# attinier84-motherboard-mk-3_0.net
KiCad netlist of a schematic drawn in EAGLE
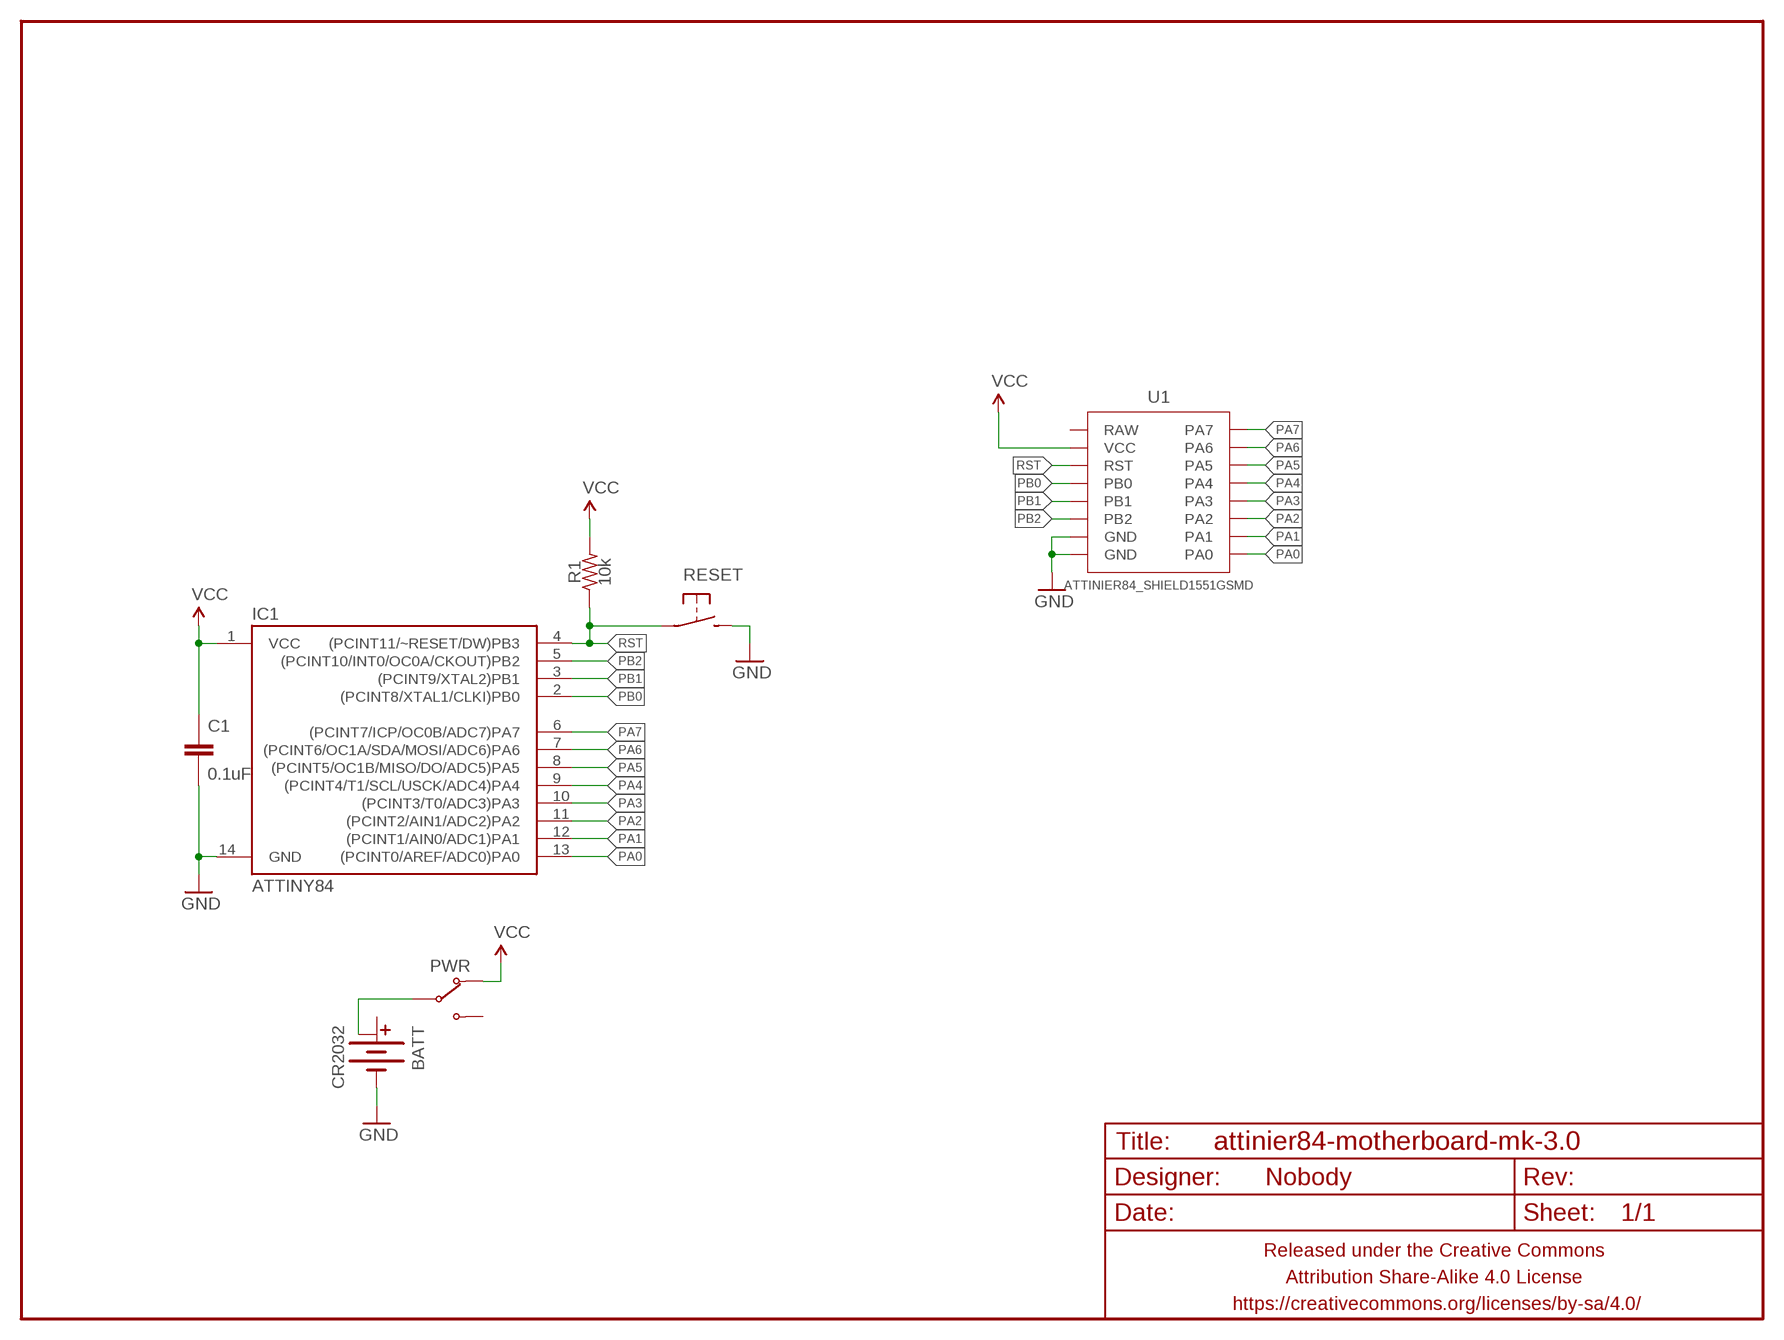
[diagram p0: schematic, sheet 1]

(export (version "E")
  (design (tool "Eeschema 10.0.6"))
  (components
    (comp (ref "BATT")
      (value "CR2032")
      (footprint "eagle-import:BATTCON_20MM_MINE")
      (libsource (lib "eagle-import") (part "BATTERY-COINCR2032_SMD"))
    )
    (comp (ref "C1")
      (value "0.1uF")
      (footprint "eagle-import:C0805")
      (libsource (lib "eagle-import") (part "CAPACITOR-CERAMICC0805"))
    )
    (comp (ref "FRAME1")
      (value "FRAME-LETTERNO_PACKAGE")
      (footprint "eagle-import:DUMMY")
      (fields (field (name "DESIGNER") "Nobody"))
      (libsource (lib "eagle-import") (part "FRAME-LETTERNO_PACKAGE"))
    )
    (comp (ref "IC1")
      (value "ATTINY84")
      (footprint "eagle-import:SO14")
      (libsource (lib "eagle-import") (part "ATTINY84"))
    )
    (comp (ref "PWR")
      (value "SWITCH-SPDTPTH-RA-2.54MM")
      (footprint "eagle-import:SPDT-RA-2.54MM")
      (libsource (lib "eagle-import") (part "SWITCH-SPDTPTH-RA-2.54MM"))
    )
    (comp (ref "R1")
      (value "10k")
      (footprint "eagle-import:R0805")
      (libsource (lib "eagle-import") (part "RESISTORR0805"))
    )
    (comp (ref "RESET")
      (value "SPST-NO-TACT3MM-RA")
      (footprint "eagle-import:TACTILE-PTH-SIDE")
      (libsource (lib "eagle-import") (part "SPST-NO-TACT3MM-RA"))
    )
    (comp (ref "U1")
      (value "ATTINIER84_SHIELD1551GSMD")
      (footprint "eagle-import:ATTINIER84_SHIELD2_SMD")
      (libsource (lib "eagle-import") (part "ATTINIER84_SHIELD1551GSMD"))
    )
  )
  (nets
    (net (code "1") (name "GND") (class "Default")
      (node (ref "BATT") (pin "BOTTOM") (pinfunction "-_BOTTOM") (pintype "bidirectional"))
      (node (ref "C1") (pin "2") (pinfunction "2_2") (pintype "passive"))
      (node (ref "IC1") (pin "14") (pinfunction "GND_14") (pintype "bidirectional"))
      (node (ref "RESET") (pin "2") (pinfunction "2_2") (pintype "passive"))
      (node (ref "U1") (pin "GND@1") (pinfunction "GND_GND@1") (pintype "bidirectional"))
      (node (ref "U1") (pin "GND@2") (pinfunction "GND_GND@2") (pintype "bidirectional"))
    )
    (net (code "2") (name "Net-(BATT-+1)") (class "Default")
      (node (ref "BATT") (pin "TOP@2") (pinfunction "+1_TOP@2") (pintype "bidirectional"))
      (node (ref "PWR") (pin "2") (pinfunction "COM_2") (pintype "passive"))
    )
    (net (code "3") (name "PA0") (class "Default")
      (node (ref "IC1") (pin "13") (pinfunction "(PCINT0/AREF/ADC0)PA0_13") (pintype "bidirectional"))
      (node (ref "U1") (pin "PA0") (pinfunction "PA0_PA0") (pintype "bidirectional"))
    )
    (net (code "4") (name "PA1") (class "Default")
      (node (ref "IC1") (pin "12") (pinfunction "(PCINT1/AIN0/ADC1)PA1_12") (pintype "bidirectional"))
      (node (ref "U1") (pin "PA1") (pinfunction "PA1_PA1") (pintype "bidirectional"))
    )
    (net (code "5") (name "PA2") (class "Default")
      (node (ref "IC1") (pin "11") (pinfunction "(PCINT2/AIN1/ADC2)PA2_11") (pintype "bidirectional"))
      (node (ref "U1") (pin "PA2") (pinfunction "PA2_PA2") (pintype "bidirectional"))
    )
    (net (code "6") (name "PA3") (class "Default")
      (node (ref "IC1") (pin "10") (pinfunction "(PCINT3/T0/ADC3)PA3_10") (pintype "bidirectional"))
      (node (ref "U1") (pin "PA3") (pinfunction "PA3_PA3") (pintype "bidirectional"))
    )
    (net (code "7") (name "PA4") (class "Default")
      (node (ref "IC1") (pin "9") (pinfunction "(PCINT4/T1/SCL/USCK/ADC4)PA4_9") (pintype "bidirectional"))
      (node (ref "U1") (pin "PA4") (pinfunction "PA4_PA4") (pintype "bidirectional"))
    )
    (net (code "8") (name "PA5") (class "Default")
      (node (ref "IC1") (pin "8") (pinfunction "(PCINT5/OC1B/MISO/DO/ADC5)PA5_8") (pintype "bidirectional"))
      (node (ref "U1") (pin "PA5") (pinfunction "PA5_PA5") (pintype "bidirectional"))
    )
    (net (code "9") (name "PA6") (class "Default")
      (node (ref "IC1") (pin "7") (pinfunction "(PCINT6/OC1A/SDA/MOSI/ADC6)PA6_7") (pintype "bidirectional"))
      (node (ref "U1") (pin "PA6") (pinfunction "PA6_PA6") (pintype "bidirectional"))
    )
    (net (code "10") (name "PA7") (class "Default")
      (node (ref "IC1") (pin "6") (pinfunction "(PCINT7/ICP/OC0B/ADC7)PA7_6") (pintype "bidirectional"))
      (node (ref "U1") (pin "PA7") (pinfunction "PA7_PA7") (pintype "bidirectional"))
    )
    (net (code "11") (name "PB0") (class "Default")
      (node (ref "IC1") (pin "2") (pinfunction "(PCINT8/XTAL1/CLKI)PB0_2") (pintype "bidirectional"))
      (node (ref "U1") (pin "PB0") (pinfunction "PB0_PB0") (pintype "bidirectional"))
    )
    (net (code "12") (name "PB1") (class "Default")
      (node (ref "IC1") (pin "3") (pinfunction "(PCINT9/XTAL2)PB1_3") (pintype "bidirectional"))
      (node (ref "U1") (pin "PB1") (pinfunction "PB1_PB1") (pintype "bidirectional"))
    )
    (net (code "13") (name "PB2") (class "Default")
      (node (ref "IC1") (pin "5") (pinfunction "(PCINT10/INT0/OC0A/CKOUT)PB2_5") (pintype "bidirectional"))
      (node (ref "U1") (pin "PB2") (pinfunction "PB2_PB2") (pintype "bidirectional"))
    )
    (net (code "14") (name "RST") (class "Default")
      (node (ref "IC1") (pin "4") (pinfunction "(PCINT11/~{RESET/DW})PB3_4") (pintype "bidirectional"))
      (node (ref "R1") (pin "1") (pinfunction "1_1") (pintype "passive"))
      (node (ref "RESET") (pin "1") (pinfunction "1_1") (pintype "passive"))
      (node (ref "U1") (pin "RST") (pinfunction "RST_RST") (pintype "bidirectional"))
    )
    (net (code "15") (name "VCC") (class "Default")
      (node (ref "C1") (pin "1") (pinfunction "1_1") (pintype "passive"))
      (node (ref "IC1") (pin "1") (pinfunction "VCC_1") (pintype "bidirectional"))
      (node (ref "PWR") (pin "1") (pinfunction "NC_1") (pintype "passive"))
      (node (ref "R1") (pin "2") (pinfunction "2_2") (pintype "passive"))
      (node (ref "U1") (pin "VCC") (pinfunction "VCC_VCC") (pintype "bidirectional"))
    )
    (net (code "16") (name "unconnected-(BATT-+-PadTOP@1)") (class "Default")
      (node (ref "BATT") (pin "TOP@1") (pinfunction "+_TOP@1") (pintype "bidirectional"))
    )
    (net (code "17") (name "unconnected-(PWR-NO-Pad3)") (class "Default")
      (node (ref "PWR") (pin "3") (pinfunction "NO_3") (pintype "passive"))
    )
    (net (code "18") (name "unconnected-(U1-PadRAW)") (class "Default")
      (node (ref "U1") (pin "RAW") (pinfunction "RAW_RAW") (pintype "bidirectional"))
    )
  )
)
